# PCM2706.net
KiCad netlist of a schematic drawn in Altium Designer
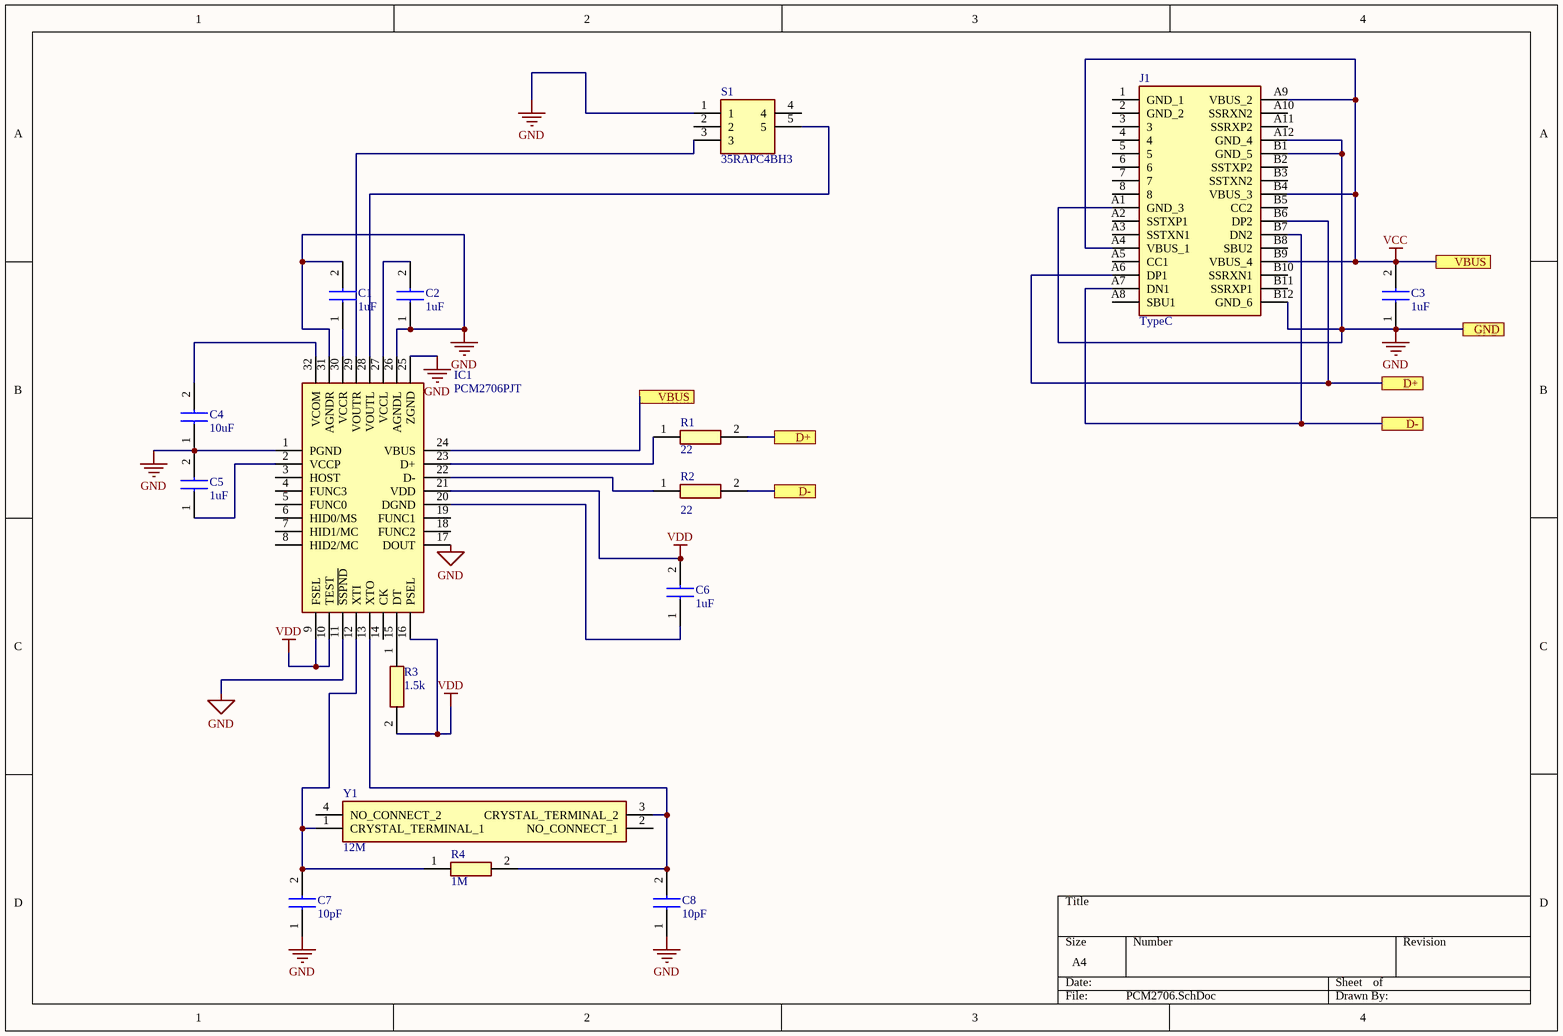
[diagram p0: PCM2706.SchDoc]

(export (version "E")
  (design (tool "Eeschema 10.0.6"))
  (components
    (comp (ref "C1")
      (value "1uF")
      (footprint "SamacSys:CAPC3216X229N")
      (description "Capacitor")
      (fields
        (field (name "MANUFACTURER_PART_NUMBER") "1206DD106KAT2A")
        (field (name "MOUSER PART NUMBER") "581-1206DD106KAT2A")
      )
      (libsource (lib "*") (part "1206DD106KAT2A"))
    )
    (comp (ref "C2")
      (value "1uF")
      (footprint "SamacSys:CAPC3216X229N")
      (description "Capacitor")
      (fields
        (field (name "MANUFACTURER_PART_NUMBER") "1206DD106KAT2A")
        (field (name "MOUSER PART NUMBER") "581-1206DD106KAT2A")
      )
      (libsource (lib "*") (part "1206DD106KAT2A"))
    )
    (comp (ref "C3")
      (value "1uF")
      (footprint "SamacSys:CAPC3216X229N")
      (description "Capacitor")
      (fields
        (field (name "MANUFACTURER_PART_NUMBER") "1206DD106KAT2A")
        (field (name "MOUSER PART NUMBER") "581-1206DD106KAT2A")
      )
      (libsource (lib "*") (part "1206DD106KAT2A"))
    )
    (comp (ref "C4")
      (value "10uF")
      (footprint "SamacSys:CAPC3216X229N")
      (description "Capacitor")
      (fields
        (field (name "MANUFACTURER_PART_NUMBER") "1206DD106KAT2A")
        (field (name "MOUSER PART NUMBER") "581-1206DD106KAT2A")
      )
      (libsource (lib "*") (part "1206DD106KAT2A"))
    )
    (comp (ref "C5")
      (value "1uF")
      (footprint "SamacSys:CAPC3216X229N")
      (description "Capacitor")
      (fields
        (field (name "MANUFACTURER_PART_NUMBER") "1206DD106KAT2A")
        (field (name "MOUSER PART NUMBER") "581-1206DD106KAT2A")
      )
      (libsource (lib "*") (part "1206DD106KAT2A"))
    )
    (comp (ref "C6")
      (value "1uF")
      (footprint "SamacSys:CAPC3216X229N")
      (description "Capacitor")
      (fields
        (field (name "MANUFACTURER_PART_NUMBER") "1206DD106KAT2A")
        (field (name "MOUSER PART NUMBER") "581-1206DD106KAT2A")
      )
      (libsource (lib "*") (part "1206DD106KAT2A"))
    )
    (comp (ref "C7")
      (value "10pF")
      (footprint "SamacSys:CAPC3216X229N")
      (description "Capacitor")
      (fields
        (field (name "MANUFACTURER_PART_NUMBER") "1206DD106KAT2A")
        (field (name "MOUSER PART NUMBER") "581-1206DD106KAT2A")
      )
      (libsource (lib "*") (part "1206DD106KAT2A"))
    )
    (comp (ref "C8")
      (value "10pF")
      (footprint "SamacSys:CAPC3216X229N")
      (description "Capacitor")
      (fields
        (field (name "MANUFACTURER_PART_NUMBER") "1206DD106KAT2A")
        (field (name "MOUSER PART NUMBER") "581-1206DD106KAT2A")
      )
      (libsource (lib "*") (part "1206DD106KAT2A"))
    )
    (comp (ref "IC1")
      (value "PCM2706PJT")
      (footprint "SamacSys:QFP80P900X900X120-32N")
      (description "Integrated Circuit")
      (fields (field (name "MOUSER PART NUMBER") "595-PCM2706PJT"))
      (libsource (lib "*") (part "PCM2706PJT"))
    )
    (comp (ref "J1")
      (value "TypeC")
      (footprint "SamacSys:632723300011")
      (description "Connector")
      (fields
        (field (name "MANUFACTURER_PART_NUMBER") "632723300011")
        (field (name "MOUSER PART NUMBER") "710-632723300011")
      )
      (libsource (lib "*") (part "632723300011"))
    )
    (comp (ref "R1")
      (value "22")
      (footprint "SamacSys:RESC3116X65N")
      (description "Resistor")
      (fields
        (field (name "MANUFACTURER_PART_NUMBER") "RC1206FR-072K49L")
        (field (name "MOUSER PART NUMBER") "603-RC1206FR-072K49L")
      )
      (libsource (lib "*") (part "RC1206FR-072K49L"))
    )
    (comp (ref "R2")
      (value "22")
      (footprint "SamacSys:RESC3116X65N")
      (description "Resistor")
      (fields
        (field (name "MANUFACTURER_PART_NUMBER") "RC1206FR-072K49L")
        (field (name "MOUSER PART NUMBER") "603-RC1206FR-072K49L")
      )
      (libsource (lib "*") (part "RC1206FR-072K49L"))
    )
    (comp (ref "R3")
      (value "1.5k")
      (footprint "SamacSys:RESC3116X65N")
      (description "Resistor")
      (fields
        (field (name "MANUFACTURER_PART_NUMBER") "RC1206FR-072K49L")
        (field (name "MOUSER PART NUMBER") "603-RC1206FR-072K49L")
      )
      (libsource (lib "") (part "RC1206FR-072K49L_1"))
    )
    (comp (ref "R4")
      (value "1M")
      (footprint "SamacSys:RESC3116X65N")
      (description "Resistor")
      (fields
        (field (name "MANUFACTURER_PART_NUMBER") "RC1206FR-072K49L")
        (field (name "MOUSER PART NUMBER") "603-RC1206FR-072K49L")
      )
      (libsource (lib "*") (part "RC1206FR-072K49L"))
    )
    (comp (ref "S1")
      (value "35RAPC4BH3")
      (footprint "SamacSys:35RAPC4BH3")
      (description "Switch")
      (fields (field (name "MOUSER PART NUMBER") "502-35RAPC4BH3"))
      (libsource (lib "*") (part "35RAPC4BH3"))
    )
    (comp (ref "Y1")
      (value "12M")
      (footprint "SamacSys:XRCGB24M000F2P00R0")
      (description "Crystal or Oscillator")
      (fields
        (field (name "MANUFACTURER_PART_NUMBER") "XRCGB24M000F2P00R0")
        (field (name "MOUSER PART NUMBER") "81-XRCGB24M000F2P0R0")
      )
      (libsource (lib "*") (part "XRCGB24M000F2P00R0"))
    )
  )
  (nets
    (net (code "1") (name "/D+") (class "Default")
      (node (ref "J1") (pin "A6") (pinfunction "DP1_A6") (pintype "passive"))
      (node (ref "J1") (pin "B6") (pinfunction "DP2_B6") (pintype "passive"))
      (node (ref "R1") (pin "2") (pinfunction "2_2") (pintype "passive"))
    )
    (net (code "2") (name "/D-") (class "Default")
      (node (ref "J1") (pin "A7") (pinfunction "DN1_A7") (pintype "passive"))
      (node (ref "J1") (pin "B7") (pinfunction "DN2_B7") (pintype "passive"))
      (node (ref "R2") (pin "2") (pinfunction "2_2") (pintype "passive"))
    )
    (net (code "3") (name "GND") (class "Default")
      (node (ref "C1") (pin "2") (pinfunction "2_2") (pintype "passive"))
      (node (ref "C2") (pin "1") (pinfunction "1_1") (pintype "passive"))
      (node (ref "C3") (pin "1") (pinfunction "1_1") (pintype "passive"))
      (node (ref "C4") (pin "1") (pinfunction "1_1") (pintype "passive"))
      (node (ref "C5") (pin "2") (pinfunction "2_2") (pintype "passive"))
      (node (ref "C7") (pin "1") (pinfunction "1_1") (pintype "passive"))
      (node (ref "C8") (pin "1") (pinfunction "1_1") (pintype "passive"))
      (node (ref "IC1") (pin "1") (pinfunction "PGND_1") (pintype "passive"))
      (node (ref "IC1") (pin "11") (pinfunction "~{SSPND}_11") (pintype "passive"))
      (node (ref "IC1") (pin "17") (pinfunction "DOUT_17") (pintype "passive"))
      (node (ref "IC1") (pin "25") (pinfunction "ZGND_25") (pintype "passive"))
      (node (ref "IC1") (pin "26") (pinfunction "AGNDL_26") (pintype "passive"))
      (node (ref "IC1") (pin "31") (pinfunction "AGNDR_31") (pintype "passive"))
      (node (ref "J1") (pin "A1") (pinfunction "GND_3_A1") (pintype "passive"))
      (node (ref "J1") (pin "A12") (pinfunction "GND_4_A12") (pintype "passive"))
      (node (ref "J1") (pin "B1") (pinfunction "GND_5_B1") (pintype "passive"))
      (node (ref "J1") (pin "B12") (pinfunction "GND_6_B12") (pintype "passive"))
      (node (ref "S1") (pin "1") (pinfunction "1_1") (pintype "passive"))
    )
    (net (code "4") (name "Net-(IC1-D+)") (class "Default")
      (node (ref "IC1") (pin "23") (pinfunction "D+_23") (pintype "passive"))
      (node (ref "R1") (pin "1") (pinfunction "1_1") (pintype "passive"))
    )
    (net (code "5") (name "Net-(IC1-D-)") (class "Default")
      (node (ref "IC1") (pin "22") (pinfunction "D-_22") (pintype "passive"))
      (node (ref "R2") (pin "1") (pinfunction "1_1") (pintype "passive"))
    )
    (net (code "6") (name "Net-(IC1-DGND)") (class "Default")
      (node (ref "C6") (pin "1") (pinfunction "1_1") (pintype "passive"))
      (node (ref "IC1") (pin "20") (pinfunction "DGND_20") (pintype "passive"))
    )
    (net (code "7") (name "Net-(IC1-DT)") (class "Default")
      (node (ref "IC1") (pin "15") (pinfunction "DT_15") (pintype "passive"))
      (node (ref "R3") (pin "1") (pinfunction "1_1") (pintype "passive"))
    )
    (net (code "8") (name "Net-(IC1-VCCL)") (class "Default")
      (node (ref "C2") (pin "2") (pinfunction "2_2") (pintype "passive"))
      (node (ref "IC1") (pin "27") (pinfunction "VCCL_27") (pintype "passive"))
    )
    (net (code "9") (name "Net-(IC1-VCCP)") (class "Default")
      (node (ref "C5") (pin "1") (pinfunction "1_1") (pintype "passive"))
      (node (ref "IC1") (pin "2") (pinfunction "VCCP_2") (pintype "passive"))
    )
    (net (code "10") (name "Net-(IC1-VCCR)") (class "Default")
      (node (ref "C1") (pin "1") (pinfunction "1_1") (pintype "passive"))
      (node (ref "IC1") (pin "30") (pinfunction "VCCR_30") (pintype "passive"))
    )
    (net (code "11") (name "Net-(IC1-VCOM)") (class "Default")
      (node (ref "C4") (pin "2") (pinfunction "2_2") (pintype "passive"))
      (node (ref "IC1") (pin "32") (pinfunction "VCOM_32") (pintype "passive"))
    )
    (net (code "12") (name "Net-(IC1-VOUTL)") (class "Default")
      (node (ref "IC1") (pin "28") (pinfunction "VOUTL_28") (pintype "passive"))
      (node (ref "S1") (pin "5") (pinfunction "5_5") (pintype "passive"))
    )
    (net (code "13") (name "Net-(IC1-VOUTR)") (class "Default")
      (node (ref "IC1") (pin "29") (pinfunction "VOUTR_29") (pintype "passive"))
      (node (ref "S1") (pin "3") (pinfunction "3_3") (pintype "passive"))
    )
    (net (code "14") (name "Net-(IC1-XTI)") (class "Default")
      (node (ref "C7") (pin "2") (pinfunction "2_2") (pintype "passive"))
      (node (ref "IC1") (pin "12") (pinfunction "XTI_12") (pintype "passive"))
      (node (ref "R4") (pin "1") (pinfunction "1_1") (pintype "passive"))
      (node (ref "Y1") (pin "1") (pinfunction "CRYSTAL_TERMINAL_1_1") (pintype "passive"))
    )
    (net (code "15") (name "Net-(IC1-XTO)") (class "Default")
      (node (ref "C8") (pin "2") (pinfunction "2_2") (pintype "passive"))
      (node (ref "IC1") (pin "13") (pinfunction "XTO_13") (pintype "passive"))
      (node (ref "R4") (pin "2") (pinfunction "2_2") (pintype "passive"))
      (node (ref "Y1") (pin "3") (pinfunction "CRYSTAL_TERMINAL_2_3") (pintype "passive"))
    )
    (net (code "16") (name "VCC") (class "Default")
      (node (ref "C3") (pin "2") (pinfunction "2_2") (pintype "passive"))
      (node (ref "IC1") (pin "24") (pinfunction "VBUS_24") (pintype "passive"))
      (node (ref "J1") (pin "A4") (pinfunction "VBUS_1_A4") (pintype "passive"))
      (node (ref "J1") (pin "A9") (pinfunction "VBUS_2_A9") (pintype "passive"))
      (node (ref "J1") (pin "B4") (pinfunction "VBUS_3_B4") (pintype "passive"))
      (node (ref "J1") (pin "B9") (pinfunction "VBUS_4_B9") (pintype "passive"))
    )
    (net (code "17") (name "VDD") (class "Default")
      (node (ref "C6") (pin "2") (pinfunction "2_2") (pintype "passive"))
      (node (ref "IC1") (pin "10") (pinfunction "TEST_10") (pintype "passive"))
      (node (ref "IC1") (pin "16") (pinfunction "PSEL_16") (pintype "passive"))
      (node (ref "IC1") (pin "21") (pinfunction "VDD_21") (pintype "passive"))
      (node (ref "IC1") (pin "9") (pinfunction "FSEL_9") (pintype "passive"))
      (node (ref "R3") (pin "2") (pinfunction "2_2") (pintype "passive"))
    )
    (net (code "18") (name "unconnected-(IC1-CK-Pad14)") (class "Default")
      (node (ref "IC1") (pin "14") (pinfunction "CK_14") (pintype "passive"))
    )
    (net (code "19") (name "unconnected-(IC1-FUNC0-Pad5)") (class "Default")
      (node (ref "IC1") (pin "5") (pinfunction "FUNC0_5") (pintype "passive"))
    )
    (net (code "20") (name "unconnected-(IC1-FUNC1-Pad19)") (class "Default")
      (node (ref "IC1") (pin "19") (pinfunction "FUNC1_19") (pintype "passive"))
    )
    (net (code "21") (name "unconnected-(IC1-FUNC2-Pad18)") (class "Default")
      (node (ref "IC1") (pin "18") (pinfunction "FUNC2_18") (pintype "passive"))
    )
    (net (code "22") (name "unconnected-(IC1-FUNC3-Pad4)") (class "Default")
      (node (ref "IC1") (pin "4") (pinfunction "FUNC3_4") (pintype "passive"))
    )
    (net (code "23") (name "unconnected-(IC1-HID0{slash}MS-Pad6)") (class "Default")
      (node (ref "IC1") (pin "6") (pinfunction "HID0/MS_6") (pintype "passive"))
    )
    (net (code "24") (name "unconnected-(IC1-HID1{slash}MC-Pad7)") (class "Default")
      (node (ref "IC1") (pin "7") (pinfunction "HID1/MC_7") (pintype "passive"))
    )
    (net (code "25") (name "unconnected-(IC1-HID2{slash}MC-Pad8)") (class "Default")
      (node (ref "IC1") (pin "8") (pinfunction "HID2/MC_8") (pintype "passive"))
    )
    (net (code "26") (name "unconnected-(IC1-HOST-Pad3)") (class "Default")
      (node (ref "IC1") (pin "3") (pinfunction "HOST_3") (pintype "passive"))
    )
    (net (code "27") (name "unconnected-(J1-CC1-PadA5)") (class "Default")
      (node (ref "J1") (pin "A5") (pinfunction "CC1_A5") (pintype "passive"))
    )
    (net (code "28") (name "unconnected-(J1-CC2-PadB5)") (class "Default")
      (node (ref "J1") (pin "B5") (pinfunction "CC2_B5") (pintype "passive"))
    )
    (net (code "29") (name "unconnected-(J1-GND_1-Pad1)") (class "Default")
      (node (ref "J1") (pin "1") (pinfunction "GND_1_1") (pintype "passive"))
    )
    (net (code "30") (name "unconnected-(J1-GND_2-Pad2)") (class "Default")
      (node (ref "J1") (pin "2") (pinfunction "GND_2_2") (pintype "passive"))
    )
    (net (code "31") (name "unconnected-(J1-Pad3)") (class "Default")
      (node (ref "J1") (pin "3") (pinfunction "3_3") (pintype "passive"))
    )
    (net (code "32") (name "unconnected-(J1-Pad4)") (class "Default")
      (node (ref "J1") (pin "4") (pinfunction "4_4") (pintype "passive"))
    )
    (net (code "33") (name "unconnected-(J1-Pad5)") (class "Default")
      (node (ref "J1") (pin "5") (pinfunction "5_5") (pintype "passive"))
    )
    (net (code "34") (name "unconnected-(J1-Pad6)") (class "Default")
      (node (ref "J1") (pin "6") (pinfunction "6_6") (pintype "passive"))
    )
    (net (code "35") (name "unconnected-(J1-Pad7)") (class "Default")
      (node (ref "J1") (pin "7") (pinfunction "7_7") (pintype "passive"))
    )
    (net (code "36") (name "unconnected-(J1-Pad8)") (class "Default")
      (node (ref "J1") (pin "8") (pinfunction "8_8") (pintype "passive"))
    )
    (net (code "37") (name "unconnected-(J1-SBU1-PadA8)") (class "Default")
      (node (ref "J1") (pin "A8") (pinfunction "SBU1_A8") (pintype "passive"))
    )
    (net (code "38") (name "unconnected-(J1-SBU2-PadB8)") (class "Default")
      (node (ref "J1") (pin "B8") (pinfunction "SBU2_B8") (pintype "passive"))
    )
    (net (code "39") (name "unconnected-(J1-SSRXN1-PadB10)") (class "Default")
      (node (ref "J1") (pin "B10") (pinfunction "SSRXN1_B10") (pintype "passive"))
    )
    (net (code "40") (name "unconnected-(J1-SSRXN2-PadA10)") (class "Default")
      (node (ref "J1") (pin "A10") (pinfunction "SSRXN2_A10") (pintype "passive"))
    )
    (net (code "41") (name "unconnected-(J1-SSRXP1-PadB11)") (class "Default")
      (node (ref "J1") (pin "B11") (pinfunction "SSRXP1_B11") (pintype "passive"))
    )
    (net (code "42") (name "unconnected-(J1-SSRXP2-PadA11)") (class "Default")
      (node (ref "J1") (pin "A11") (pinfunction "SSRXP2_A11") (pintype "passive"))
    )
    (net (code "43") (name "unconnected-(J1-SSTXN1-PadA3)") (class "Default")
      (node (ref "J1") (pin "A3") (pinfunction "SSTXN1_A3") (pintype "passive"))
    )
    (net (code "44") (name "unconnected-(J1-SSTXN2-PadB3)") (class "Default")
      (node (ref "J1") (pin "B3") (pinfunction "SSTXN2_B3") (pintype "passive"))
    )
    (net (code "45") (name "unconnected-(J1-SSTXP1-PadA2)") (class "Default")
      (node (ref "J1") (pin "A2") (pinfunction "SSTXP1_A2") (pintype "passive"))
    )
    (net (code "46") (name "unconnected-(J1-SSTXP2-PadB2)") (class "Default")
      (node (ref "J1") (pin "B2") (pinfunction "SSTXP2_B2") (pintype "passive"))
    )
    (net (code "47") (name "unconnected-(S1-Pad2)") (class "Default")
      (node (ref "S1") (pin "2") (pinfunction "2_2") (pintype "passive"))
    )
    (net (code "48") (name "unconnected-(S1-Pad4)") (class "Default")
      (node (ref "S1") (pin "4") (pinfunction "4_4") (pintype "passive"))
    )
    (net (code "49") (name "unconnected-(Y1-NO_CONNECT_1-Pad2)") (class "Default")
      (node (ref "Y1") (pin "2") (pinfunction "NO_CONNECT_1_2") (pintype "passive"))
    )
    (net (code "50") (name "unconnected-(Y1-NO_CONNECT_2-Pad4)") (class "Default")
      (node (ref "Y1") (pin "4") (pinfunction "NO_CONNECT_2_4") (pintype "passive"))
    )
  )
)
